# Project-TSC.net
KiCad netlist of a schematic drawn in EAGLE
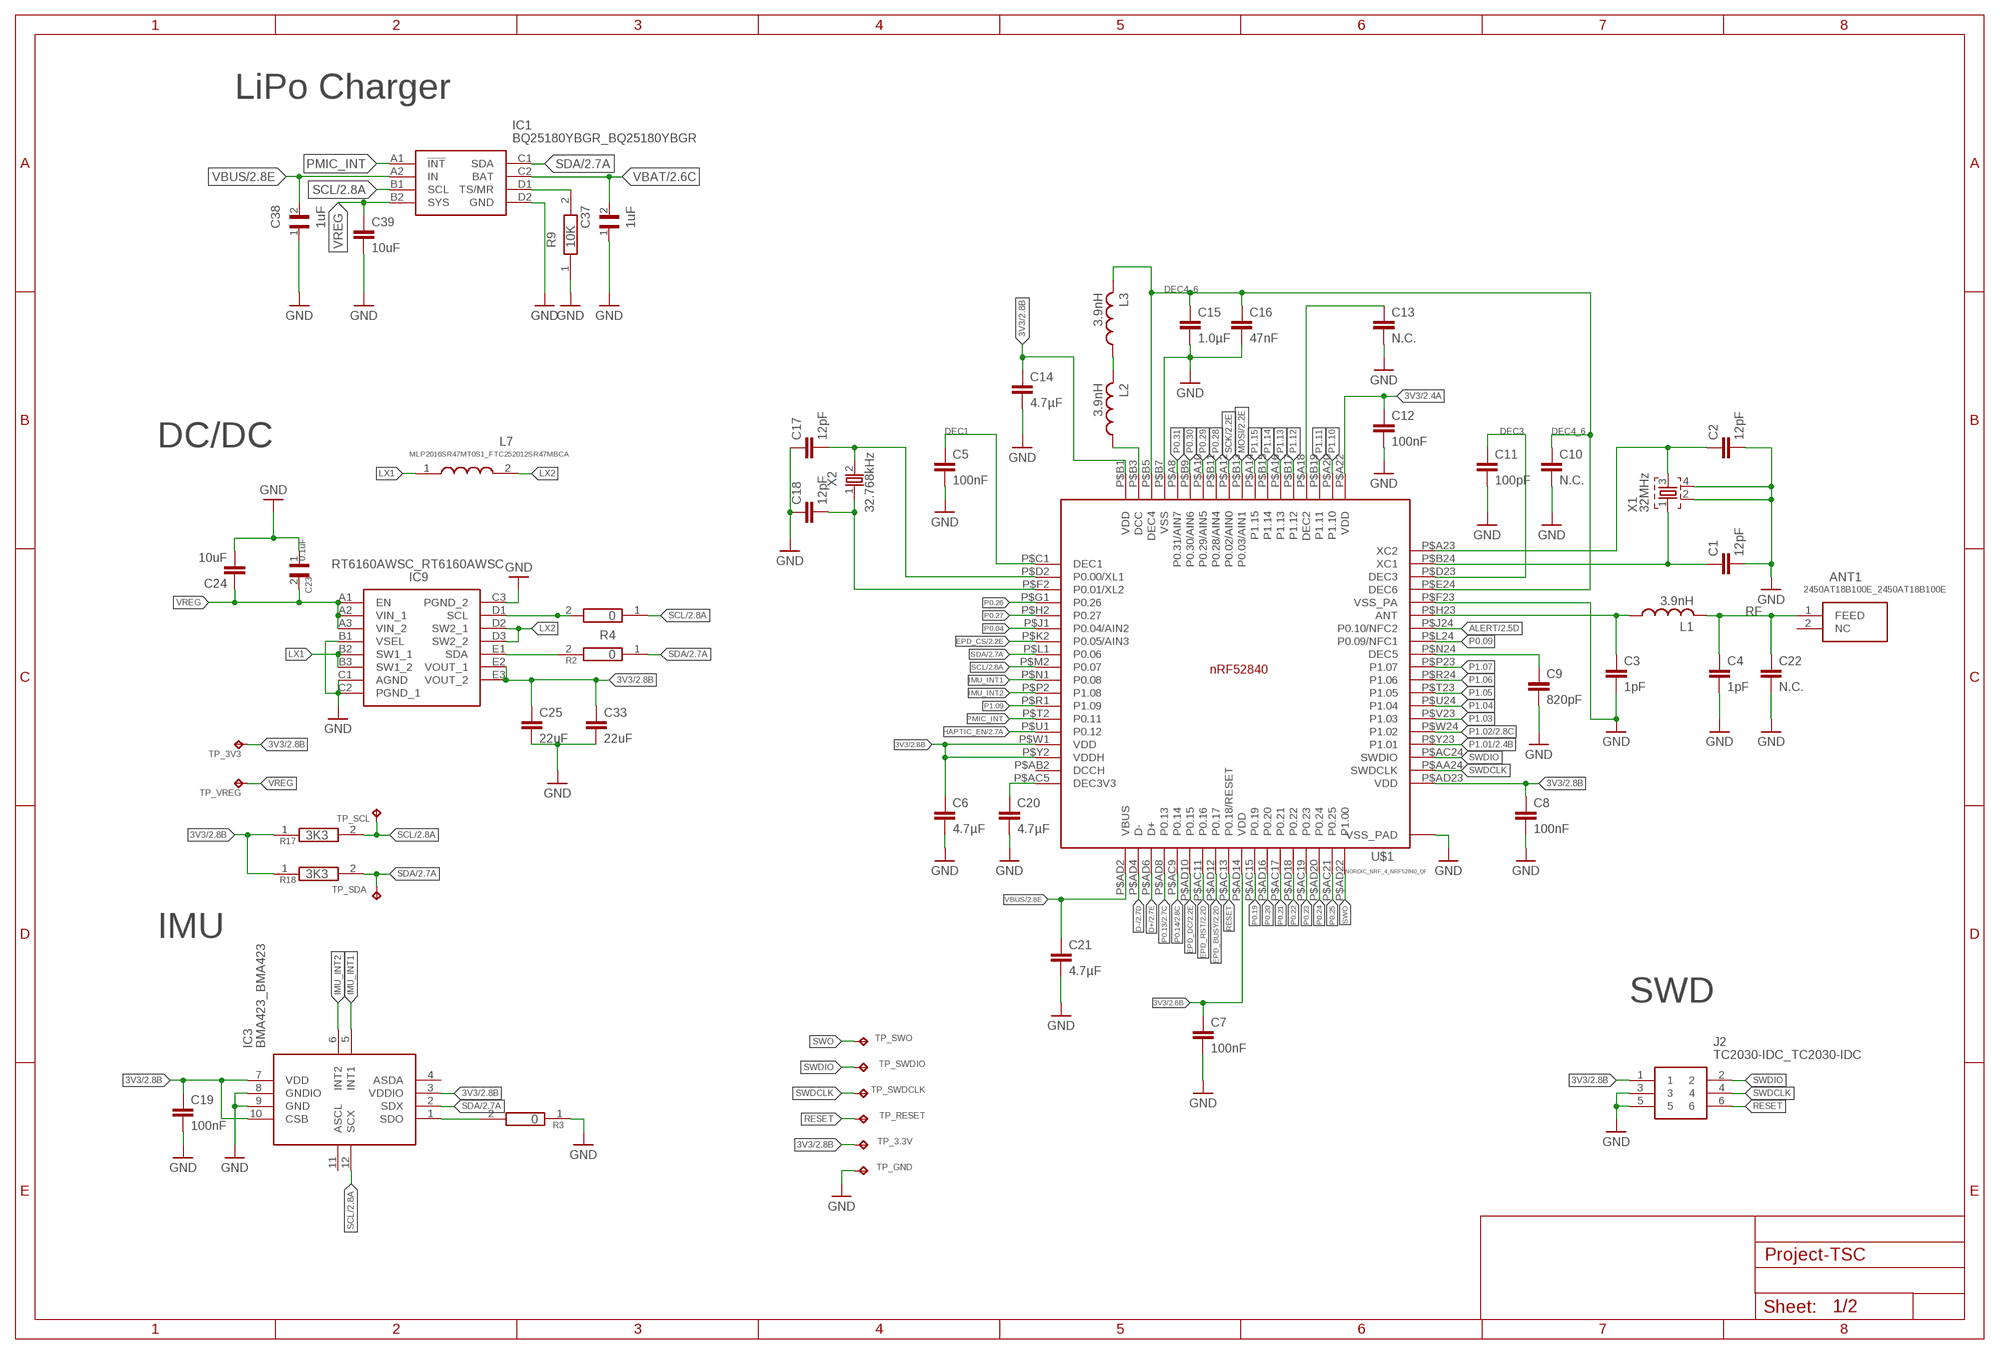
[diagram p0: schematic, sheet 1]
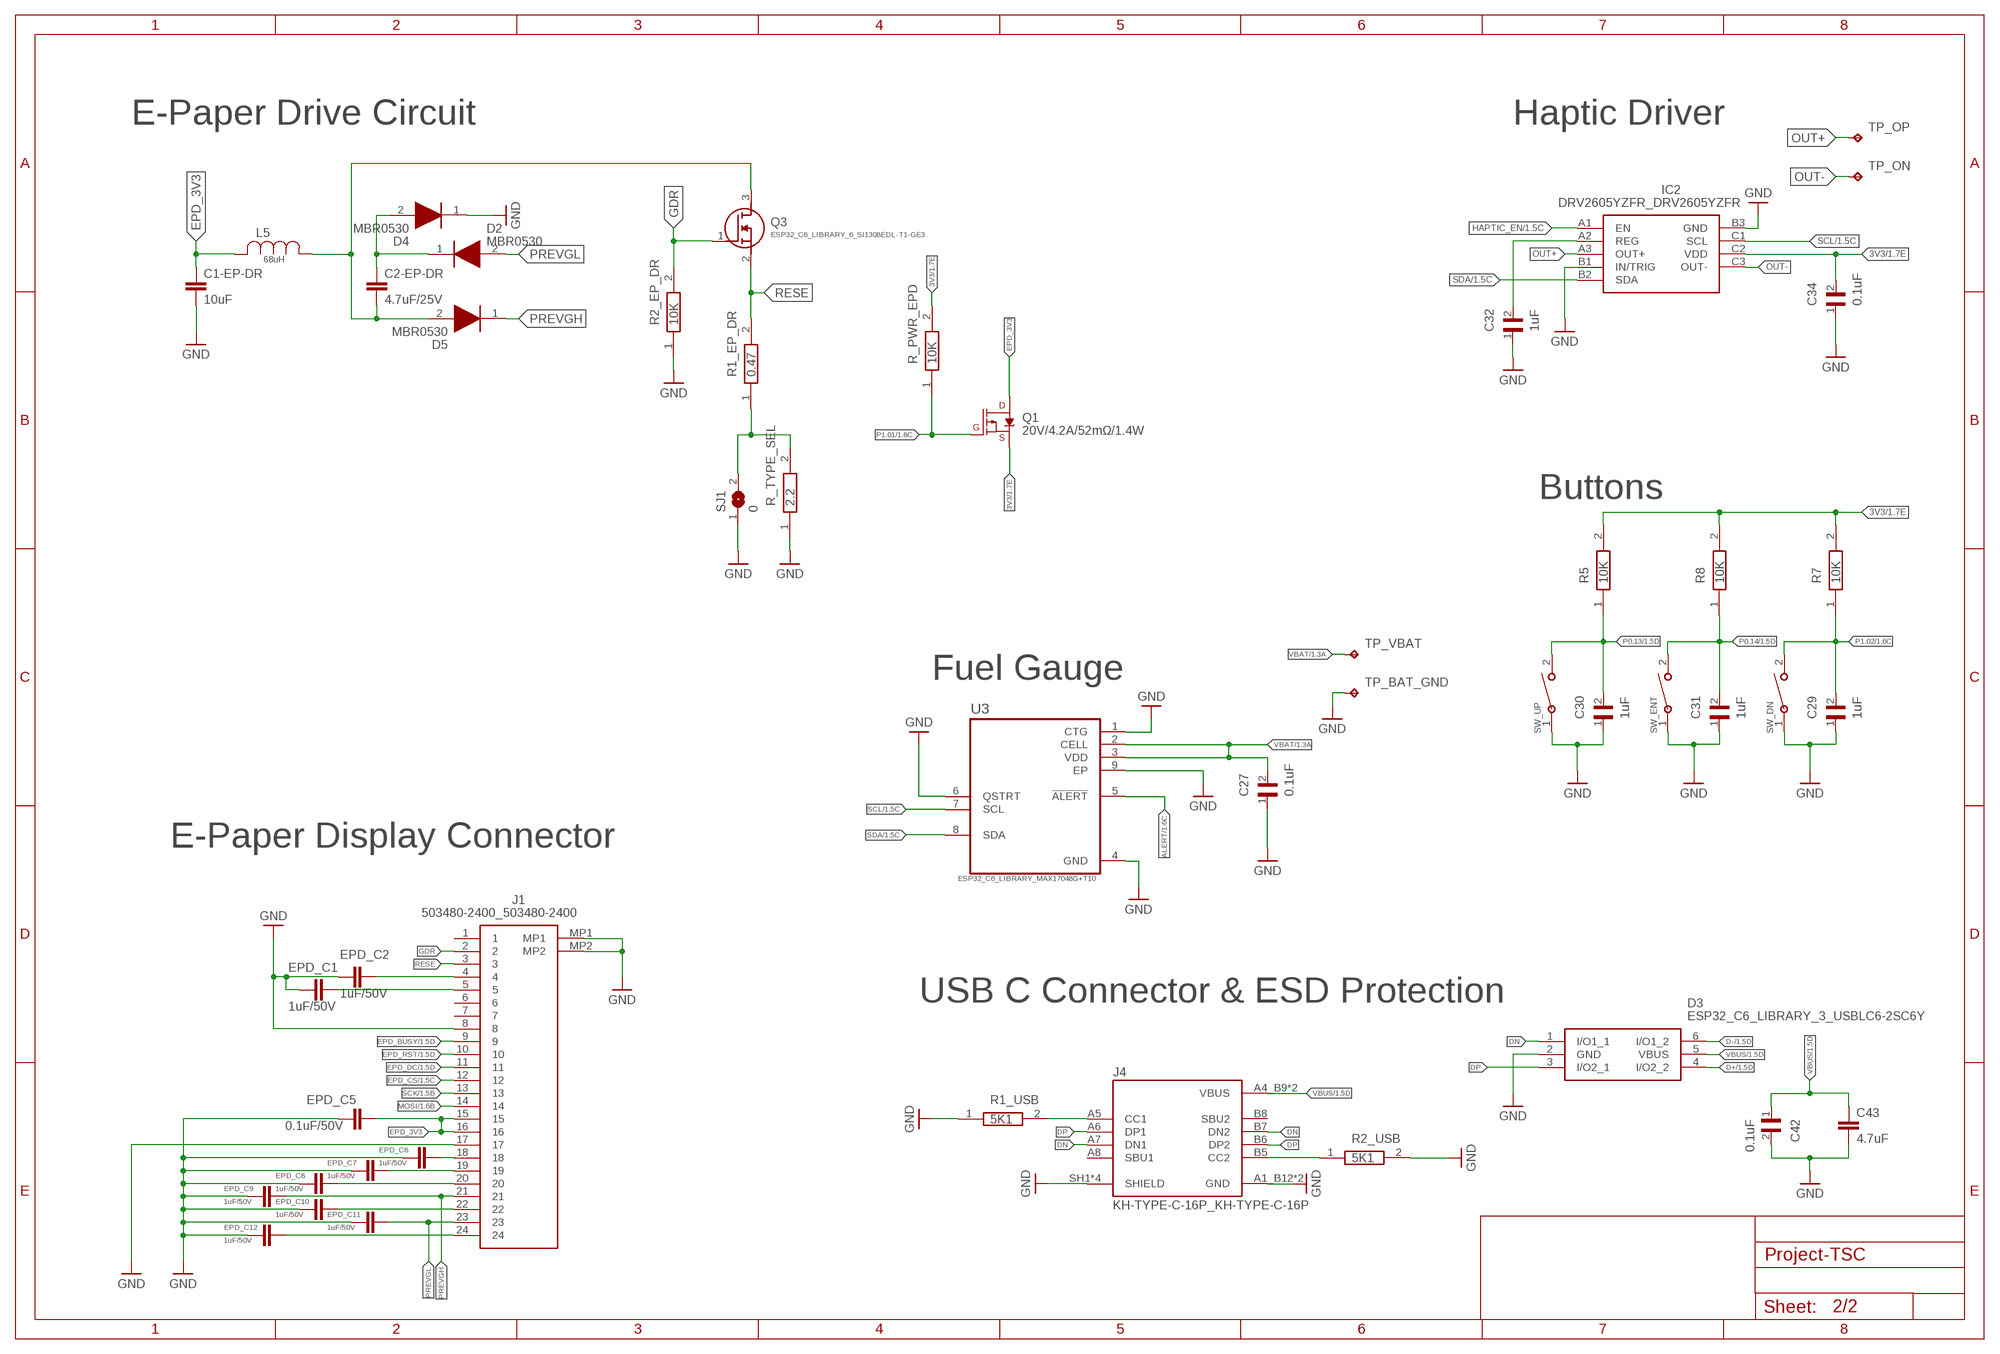
[diagram p1: schematic, sheet 2]

(export (version "E")
  (design (tool "Eeschema 10.0.6"))
  (components
    (comp (ref "ANT1")
      (value "2450AT18B100E_2450AT18B100E")
      (footprint "eagle-import:2450AT18B100E_ANTC3216X140N")
      (fields
        (field (name "ARROW_PART_NUMBER") "2450AT18B100E")
        (field (name "MOUSER_PART_NUMBER") "609-2450AT18B100E")
      )
      (libsource (lib "eagle-import") (part "2450AT18B100E_2450AT18B100E"))
    )
    (comp (ref "C1")
      (value "12pF")
      (footprint "eagle-import:NORDIC_NRF_3_RESC0201_L")
      (libsource (lib "eagle-import") (part "NORDIC_NRF_3_CAPACITOR_0201_L"))
    )
    (comp (ref "C2")
      (value "12pF")
      (footprint "eagle-import:NORDIC_NRF_3_RESC0201_L")
      (libsource (lib "eagle-import") (part "NORDIC_NRF_3_CAPACITOR_0201_L"))
    )
    (comp (ref "C3")
      (value "1pF")
      (footprint "eagle-import:NORDIC_NRF_3_RESC0201_L")
      (libsource (lib "eagle-import") (part "NORDIC_NRF_3_CAPACITOR_0201_L"))
    )
    (comp (ref "C4")
      (value "1pF")
      (footprint "eagle-import:NORDIC_NRF_3_RESC0201_L")
      (libsource (lib "eagle-import") (part "NORDIC_NRF_3_CAPACITOR_0201_L"))
    )
    (comp (ref "C5")
      (value "100nF")
      (footprint "eagle-import:NORDIC_NRF_3_RESC0201_L")
      (libsource (lib "eagle-import") (part "NORDIC_NRF_3_CAPACITOR_0201_L"))
    )
    (comp (ref "C6")
      (value "4.7µF")
      (footprint "eagle-import:PERFECT_0402_0402")
      (libsource (lib "eagle-import") (part "PERFECT_0402_CAP_0402"))
    )
    (comp (ref "C7")
      (value "100nF")
      (footprint "eagle-import:NORDIC_NRF_3_RESC0201_L")
      (libsource (lib "eagle-import") (part "NORDIC_NRF_3_CAPACITOR_0201_L"))
    )
    (comp (ref "C8")
      (value "100nF")
      (footprint "eagle-import:NORDIC_NRF_3_RESC0201_L")
      (libsource (lib "eagle-import") (part "NORDIC_NRF_3_CAPACITOR_0201_L"))
    )
    (comp (ref "C9")
      (value "820pF")
      (footprint "eagle-import:NORDIC_NRF_3_RESC0201_L")
      (libsource (lib "eagle-import") (part "NORDIC_NRF_3_CAPACITOR_0201_L"))
    )
    (comp (ref "C10")
      (value "N.C.")
      (footprint "eagle-import:NORDIC_NRF_3_RESC0201_L")
      (libsource (lib "eagle-import") (part "NORDIC_NRF_3_CAPACITOR_0201_L"))
    )
    (comp (ref "C11")
      (value "100pF")
      (footprint "eagle-import:NORDIC_NRF_3_RESC0201_L")
      (libsource (lib "eagle-import") (part "NORDIC_NRF_3_CAPACITOR_0201_L"))
    )
    (comp (ref "C12")
      (value "100nF")
      (footprint "eagle-import:NORDIC_NRF_3_RESC0201_L")
      (libsource (lib "eagle-import") (part "NORDIC_NRF_3_CAPACITOR_0201_L"))
    )
    (comp (ref "C13")
      (value "N.C.")
      (footprint "eagle-import:NORDIC_NRF_3_RESC0201_L")
      (libsource (lib "eagle-import") (part "NORDIC_NRF_3_CAPACITOR_0201_L"))
    )
    (comp (ref "C14")
      (value "4.7µF")
      (footprint "eagle-import:PERFECT_0402_0402")
      (libsource (lib "eagle-import") (part "PERFECT_0402_CAP_0402"))
    )
    (comp (ref "C15")
      (value "1.0µF")
      (footprint "eagle-import:PERFECT_0402_0402")
      (libsource (lib "eagle-import") (part "PERFECT_0402_CAP_0402"))
    )
    (comp (ref "C16")
      (value "47nF")
      (footprint "eagle-import:NORDIC_NRF_3_RESC0201_L")
      (libsource (lib "eagle-import") (part "NORDIC_NRF_3_CAPACITOR_0201_L"))
    )
    (comp (ref "C17")
      (value "12pF")
      (footprint "eagle-import:NORDIC_NRF_3_RESC0201_L")
      (libsource (lib "eagle-import") (part "NORDIC_NRF_3_CAPACITOR_0201_L"))
    )
    (comp (ref "C18")
      (value "12pF")
      (footprint "eagle-import:NORDIC_NRF_3_RESC0201_L")
      (libsource (lib "eagle-import") (part "NORDIC_NRF_3_CAPACITOR_0201_L"))
    )
    (comp (ref "C19")
      (value "100nF")
      (footprint "eagle-import:PERFECT_0402_0402")
      (libsource (lib "eagle-import") (part "PERFECT_0402_CAP_0402"))
    )
    (comp (ref "C20")
      (value "4.7µF")
      (footprint "eagle-import:PERFECT_0402_0402")
      (libsource (lib "eagle-import") (part "PERFECT_0402_CAP_0402"))
    )
    (comp (ref "C21")
      (value "4.7µF")
      (footprint "eagle-import:PERFECT_0402_0402")
      (libsource (lib "eagle-import") (part "PERFECT_0402_CAP_0402"))
    )
    (comp (ref "C22")
      (value "N.C.")
      (footprint "eagle-import:NORDIC_NRF_3_RESC0201_L")
      (libsource (lib "eagle-import") (part "NORDIC_NRF_3_CAPACITOR_0201_L"))
    )
    (comp (ref "C23")
      (value "0.1uF")
      (footprint "eagle-import:GRM011R60J152KE01L_1_0201")
      (libsource (lib "eagle-import") (part "GRM011R60J152KE01L_1_GRM011R60J152KE01L"))
    )
    (comp (ref "C24")
      (value "10uF")
      (footprint "eagle-import:PERFECT_0402_0402")
      (libsource (lib "eagle-import") (part "PERFECT_0402_CAP_0402"))
    )
    (comp (ref "C25")
      (value "22uF")
      (footprint "eagle-import:PERFECT_0402_0402")
      (libsource (lib "eagle-import") (part "PERFECT_0402_CAP_0402"))
    )
    (comp (ref "C33")
      (value "22uF")
      (footprint "eagle-import:PERFECT_0402_0402")
      (libsource (lib "eagle-import") (part "PERFECT_0402_CAP_0402"))
    )
    (comp (ref "C37")
      (value "1uF")
      (footprint "eagle-import:GRM011R60J152KE01L_1_0201")
      (libsource (lib "eagle-import") (part "GRM011R60J152KE01L_1_GRM011R60J152KE01L"))
    )
    (comp (ref "C38")
      (value "1uF")
      (footprint "eagle-import:GRM011R60J152KE01L_1_0201")
      (libsource (lib "eagle-import") (part "GRM011R60J152KE01L_1_GRM011R60J152KE01L"))
    )
    (comp (ref "C39")
      (value "10uF")
      (footprint "eagle-import:PERFECT_0402_0402")
      (libsource (lib "eagle-import") (part "PERFECT_0402_CAP_0402"))
    )
    (comp (ref "IC1")
      (value "BQ25180YBGR_BQ25180YBGR")
      (footprint "eagle-import:BQ25180YBGR_BGA8C40P2X4_100X155X50")
      (fields
        (field (name "ARROW_PART_NUMBER") "BQ25180YBGR")
        (field (name "MOUSER_PART_NUMBER") "595-BQ25180YBGR")
      )
      (libsource (lib "eagle-import") (part "BQ25180YBGR_BQ25180YBGR"))
    )
    (comp (ref "IC3")
      (value "BMA423_BMA423")
      (footprint "eagle-import:BMA423_BMA423")
      (fields (field (name "ARROW_PART_NUMBER") "BMA423") (field (name "MOUSER_PART_NUMBER") "262-BMA423"))
      (libsource (lib "eagle-import") (part "BMA423_BMA423"))
    )
    (comp (ref "IC9")
      (value "RT6160AWSC_RT6160AWSC")
      (footprint "eagle-import:RT6160AWSC_BGA15C40P3X5_140X230X60")
      (fields
        (field (name "MANUFACTURER_PART_NUMBER") "RT6160AWSC")
        (field (name "MOUSER_PART_NUMBER") "835-RT6160AWSC")
      )
      (libsource (lib "eagle-import") (part "RT6160AWSC_RT6160AWSC"))
    )
    (comp (ref "J2")
      (value "TC2030-IDC_TC2030-IDC")
      (footprint "eagle-import:TC2030-IDC_TC2030IDC")
      (fields (field (name "MANUFACTURER_PART_NUMBER") "TC2030-IDC"))
      (libsource (lib "eagle-import") (part "TC2030-IDC_TC2030-IDC"))
    )
    (comp (ref "L1")
      (value "3.9nH")
      (footprint "eagle-import:NORDIC_NRF_2_RESC0402_L")
      (libsource (lib "eagle-import") (part "NORDIC_NRF_2_INDUCTOR_0402_L"))
    )
    (comp (ref "L2")
      (value "3.9nH")
      (footprint "eagle-import:NORDIC_NRF_2_RESC0402_L")
      (libsource (lib "eagle-import") (part "NORDIC_NRF_2_INDUCTOR_0402_L"))
    )
    (comp (ref "L3")
      (value "3.9nH")
      (footprint "eagle-import:NORDIC_NRF_2_RESC0402_L")
      (libsource (lib "eagle-import") (part "NORDIC_NRF_2_INDUCTOR_0402_L"))
    )
    (comp (ref "L7")
      (value "MLP2016SR47MT0S1_FTC252012SR47MBCA")
      (footprint "eagle-import:MLP2016SR47MT0S1_INDC2016X100N")
      (fields (field (name "MANUFACTURER_PART_NUMBER") "FTC252012SR47MBCA"))
      (libsource (lib "eagle-import") (part "MLP2016SR47MT0S1_FTC252012SR47MBCA"))
    )
    (comp (ref "R2")
      (value "0")
      (footprint "eagle-import:CPF0201D7K68C1_0201")
      (libsource (lib "eagle-import") (part "CPF0201D7K68C1_CPF0201D7K68C1"))
    )
    (comp (ref "R3")
      (value "0")
      (footprint "eagle-import:CPF0201D7K68C1_0201")
      (libsource (lib "eagle-import") (part "CPF0201D7K68C1_CPF0201D7K68C1"))
    )
    (comp (ref "R4")
      (value "0")
      (footprint "eagle-import:CPF0201D7K68C1_0201")
      (libsource (lib "eagle-import") (part "CPF0201D7K68C1_CPF0201D7K68C1"))
    )
    (comp (ref "R9")
      (value "10K")
      (footprint "eagle-import:CPF0201D7K68C1_0201")
      (libsource (lib "eagle-import") (part "CPF0201D7K68C1_CPF0201D7K68C1"))
    )
    (comp (ref "R17")
      (value "3K3")
      (footprint "eagle-import:CPF0201D7K68C1_0201")
      (libsource (lib "eagle-import") (part "CPF0201D7K68C1_CPF0201D7K68C1"))
    )
    (comp (ref "R18")
      (value "3K3")
      (footprint "eagle-import:CPF0201D7K68C1_0201")
      (libsource (lib "eagle-import") (part "CPF0201D7K68C1_CPF0201D7K68C1"))
    )
    (comp (ref "TP_3.3V")
      (value "HECTOR_WATCH_1_TPTP20R")
      (footprint "eagle-import:HECTOR_WATCH_1_TP20R")
      (libsource (lib "eagle-import") (part "HECTOR_WATCH_1_TPTP20R"))
    )
    (comp (ref "TP_3V3")
      (value "HECTOR_WATCH_1_TPTP20R")
      (footprint "eagle-import:HECTOR_WATCH_1_TP20R")
      (libsource (lib "eagle-import") (part "HECTOR_WATCH_1_TPTP20R"))
    )
    (comp (ref "TP_GND")
      (value "HECTOR_WATCH_1_TPTP20R")
      (footprint "eagle-import:HECTOR_WATCH_1_TP20R")
      (libsource (lib "eagle-import") (part "HECTOR_WATCH_1_TPTP20R"))
    )
    (comp (ref "TP_RESET")
      (value "HECTOR_WATCH_1_TPTP20R")
      (footprint "eagle-import:HECTOR_WATCH_1_TP20R")
      (libsource (lib "eagle-import") (part "HECTOR_WATCH_1_TPTP20R"))
    )
    (comp (ref "TP_SCL")
      (value "HECTOR_WATCH_1_TPTP20R")
      (footprint "eagle-import:HECTOR_WATCH_1_TP20R")
      (libsource (lib "eagle-import") (part "HECTOR_WATCH_1_TPTP20R"))
    )
    (comp (ref "TP_SDA")
      (value "HECTOR_WATCH_1_TPTP20R")
      (footprint "eagle-import:HECTOR_WATCH_1_TP20R")
      (libsource (lib "eagle-import") (part "HECTOR_WATCH_1_TPTP20R"))
    )
    (comp (ref "TP_SWDCLK")
      (value "HECTOR_WATCH_1_TPTP20R")
      (footprint "eagle-import:HECTOR_WATCH_1_TP20R")
      (libsource (lib "eagle-import") (part "HECTOR_WATCH_1_TPTP20R"))
    )
    (comp (ref "TP_SWDIO")
      (value "HECTOR_WATCH_1_TPTP20R")
      (footprint "eagle-import:HECTOR_WATCH_1_TP20R")
      (libsource (lib "eagle-import") (part "HECTOR_WATCH_1_TPTP20R"))
    )
    (comp (ref "TP_SWO")
      (value "HECTOR_WATCH_1_TPTP20R")
      (footprint "eagle-import:HECTOR_WATCH_1_TP20R")
      (libsource (lib "eagle-import") (part "HECTOR_WATCH_1_TPTP20R"))
    )
    (comp (ref "TP_VREG")
      (value "HECTOR_WATCH_1_TPTP20R")
      (footprint "eagle-import:HECTOR_WATCH_1_TP20R")
      (libsource (lib "eagle-import") (part "HECTOR_WATCH_1_TPTP20R"))
    )
    (comp (ref "U$1")
      (value "NORDIC_NRF_4_NRF52840_QF")
      (footprint "eagle-import:NORDIC_NRF_4_AQFN50P700X700X85_HS-74N")
      (libsource (lib "eagle-import") (part "NORDIC_NRF_4_NRF52840_QF"))
    )
    (comp (ref "X1")
      (value "32MHz")
      (footprint "eagle-import:NORDIC_NRF_BT-XTAL_2016_N")
      (libsource (lib "eagle-import") (part "NORDIC_NRF_XTAL_32MHZ"))
    )
    (comp (ref "X2")
      (value "32.768kHz")
      (footprint "eagle-import:NORDIC_NRF_1_XTAL_3215_N")
      (libsource (lib "eagle-import") (part "NORDIC_NRF_1_XTAL_32KHZ"))
    )
    (comp (ref "C1-EP-DR")
      (value "10uF")
      (footprint "eagle-import:PERFECT_0402_0402")
      (libsource (lib "eagle-import") (part "PERFECT_0402_CAP_0402"))
    )
    (comp (ref "C2-EP-DR")
      (value "4.7uF/25V")
      (footprint "eagle-import:PERFECT_0402_0402")
      (libsource (lib "eagle-import") (part "PERFECT_0402_CAP_0402"))
    )
    (comp (ref "C27")
      (value "0.1uF")
      (footprint "eagle-import:GRM011R60J152KE01L_2_CAPC0201X13N")
      (fields (field (name "MF") "Murata") (field (name "MP") "GRM011R60J152KE01L"))
      (libsource (lib "eagle-import") (part "GRM011R60J152KE01L_2_GRM011R60J152KE01L"))
    )
    (comp (ref "C29")
      (value "1uF")
      (footprint "eagle-import:GRM011R60J152KE01L_2_CAPC0201X13N")
      (fields (field (name "MF") "Murata") (field (name "MP") "GRM011R60J152KE01L"))
      (libsource (lib "eagle-import") (part "GRM011R60J152KE01L_2_GRM011R60J152KE01L"))
    )
    (comp (ref "C30")
      (value "1uF")
      (footprint "eagle-import:GRM011R60J152KE01L_2_CAPC0201X13N")
      (fields (field (name "MF") "Murata") (field (name "MP") "GRM011R60J152KE01L"))
      (libsource (lib "eagle-import") (part "GRM011R60J152KE01L_2_GRM011R60J152KE01L"))
    )
    (comp (ref "C31")
      (value "1uF")
      (footprint "eagle-import:GRM011R60J152KE01L_2_CAPC0201X13N")
      (fields (field (name "MF") "Murata") (field (name "MP") "GRM011R60J152KE01L"))
      (libsource (lib "eagle-import") (part "GRM011R60J152KE01L_2_GRM011R60J152KE01L"))
    )
    (comp (ref "C32")
      (value "1uF")
      (footprint "eagle-import:GRM011R60J152KE01L_2_CAPC0201X13N")
      (fields (field (name "MF") "Murata") (field (name "MP") "GRM011R60J152KE01L"))
      (libsource (lib "eagle-import") (part "GRM011R60J152KE01L_2_GRM011R60J152KE01L"))
    )
    (comp (ref "C34")
      (value "0.1uF")
      (footprint "eagle-import:GRM011R60J152KE01L_2_CAPC0201X13N")
      (fields (field (name "MF") "Murata") (field (name "MP") "GRM011R60J152KE01L"))
      (libsource (lib "eagle-import") (part "GRM011R60J152KE01L_2_GRM011R60J152KE01L"))
    )
    (comp (ref "C42")
      (value "0.1uF")
      (footprint "eagle-import:GRM011R60J152KE01L_2_CAPC0201X13N")
      (fields (field (name "MF") "Murata") (field (name "MP") "GRM011R60J152KE01L"))
      (libsource (lib "eagle-import") (part "GRM011R60J152KE01L_2_GRM011R60J152KE01L"))
    )
    (comp (ref "C43")
      (value "4.7uF")
      (footprint "eagle-import:PERFECT_0402_0402")
      (libsource (lib "eagle-import") (part "PERFECT_0402_CAP_0402"))
    )
    (comp (ref "D2")
      (value "MBR0530")
      (footprint "eagle-import:ESP32_C6_LIBRARY_5_SOD3716X135N")
      (fields (field (name "MF") "ON Semiconductor"))
      (libsource (lib "eagle-import") (part "ESP32_C6_LIBRARY_5_MBR0530"))
    )
    (comp (ref "D3")
      (value "ESP32_C6_LIBRARY_3_USBLC6-2SC6Y")
      (footprint "eagle-import:ESP32_C6_LIBRARY_3_SOT95P280X145-6N")
      (fields (field (name "MF") "STMicroelectronics") (field (name "MP") "USBLC6-2SC6Y"))
      (libsource (lib "eagle-import") (part "ESP32_C6_LIBRARY_3_USBLC6-2SC6Y"))
    )
    (comp (ref "D4")
      (value "MBR0530")
      (footprint "eagle-import:ESP32_C6_LIBRARY_5_SOD3716X135N")
      (fields (field (name "MF") "ON Semiconductor"))
      (libsource (lib "eagle-import") (part "ESP32_C6_LIBRARY_5_MBR0530"))
    )
    (comp (ref "D5")
      (value "MBR0530")
      (footprint "eagle-import:ESP32_C6_LIBRARY_5_SOD3716X135N")
      (fields (field (name "MF") "ON Semiconductor"))
      (libsource (lib "eagle-import") (part "ESP32_C6_LIBRARY_5_MBR0530"))
    )
    (comp (ref "EPD_C1")
      (value "1uF/50V")
      (footprint "eagle-import:PERFECT_0402_0402")
      (libsource (lib "eagle-import") (part "PERFECT_0402_CAP_0402"))
    )
    (comp (ref "EPD_C2")
      (value "1uF/50V")
      (footprint "eagle-import:PERFECT_0402_0402")
      (libsource (lib "eagle-import") (part "PERFECT_0402_CAP_0402"))
    )
    (comp (ref "EPD_C5")
      (value "0.1uF/50V")
      (footprint "eagle-import:NORDIC_NRF_3_RESC0201_L")
      (libsource (lib "eagle-import") (part "NORDIC_NRF_3_CAPACITOR_0201_L"))
    )
    (comp (ref "EPD_C6")
      (value "1uF/50V")
      (footprint "eagle-import:PERFECT_0402_0402")
      (libsource (lib "eagle-import") (part "PERFECT_0402_CAP_0402"))
    )
    (comp (ref "EPD_C7")
      (value "1uF/50V")
      (footprint "eagle-import:PERFECT_0402_0402")
      (libsource (lib "eagle-import") (part "PERFECT_0402_CAP_0402"))
    )
    (comp (ref "EPD_C8")
      (value "1uF/50V")
      (footprint "eagle-import:PERFECT_0402_0402")
      (libsource (lib "eagle-import") (part "PERFECT_0402_CAP_0402"))
    )
    (comp (ref "EPD_C9")
      (value "1uF/50V")
      (footprint "eagle-import:PERFECT_0402_0402")
      (libsource (lib "eagle-import") (part "PERFECT_0402_CAP_0402"))
    )
    (comp (ref "EPD_C10")
      (value "1uF/50V")
      (footprint "eagle-import:PERFECT_0402_0402")
      (libsource (lib "eagle-import") (part "PERFECT_0402_CAP_0402"))
    )
    (comp (ref "EPD_C11")
      (value "1uF/50V")
      (footprint "eagle-import:PERFECT_0402_0402")
      (libsource (lib "eagle-import") (part "PERFECT_0402_CAP_0402"))
    )
    (comp (ref "EPD_C12")
      (value "1uF/50V")
      (footprint "eagle-import:PERFECT_0402_0402")
      (libsource (lib "eagle-import") (part "PERFECT_0402_CAP_0402"))
    )
    (comp (ref "IC2")
      (value "DRV2605YZFR_DRV2605YZFR")
      (footprint "eagle-import:DRV2605YZFR_BGA9C50P3X3_144X144X62")
      (fields (field (name "ARROW_PART_NUMBER") "DRV2605YZFR"))
      (libsource (lib "eagle-import") (part "DRV2605YZFR_DRV2605YZFR"))
    )
    (comp (ref "J1")
      (value "503480-2400_503480-2400")
      (footprint "eagle-import:503480-2400_5034802400")
      (fields
        (field (name "MANUFACTURER_PART_NUMBER") "503480-2400")
        (field (name "MOUSER_PART_NUMBER") "538-503480-2400")
      )
      (libsource (lib "eagle-import") (part "503480-2400_503480-2400"))
    )
    (comp (ref "J4")
      (value "KH-TYPE-C-16P_KH-TYPE-C-16P")
      (footprint "eagle-import:KH-TYPE-C-16P_KINGHELM_KH-TYPE-C-16P")
      (fields (field (name "MF") "kinghelm") (field (name "MP") "KH-TYPE-C-16P"))
      (libsource (lib "eagle-import") (part "KH-TYPE-C-16P_KH-TYPE-C-16P"))
    )
    (comp (ref "L5")
      (value "68uH")
      (footprint "eagle-import:ESP32_C6_LIBRARY_2_IND_4828-WE-TPC_WRE")
      (fields
        (field (name "MANUFACTURER_PART_NUMBER") "744043680")
        (field (name "COPYRIGHT") "Copyright (C) 2024 Ultra Librarian. All rights reserved.")
      )
      (libsource (lib "eagle-import") (part "ESP32_C6_LIBRARY_2_744043680IND_4828-WE-TPC_WRE"))
    )
    (comp (ref "Q1")
      (value "20V/4.2A/52mΩ/1.4W")
      (footprint "eagle-import:ESP32_C6_LIBRARY_4_ESP32_C6_LIBRARY_4_ESP32_C6_LIBRARY_4_ESP32_C6_LIBRARY_4_ESP32_WROVER_SPARKFUN-DISCRETESEMI_SOT23-3")
      (libsource (lib "eagle-import") (part "ESP32_C6_LIBRARY_4_ESP32_WROVER_SPARKFUN-DISCRETESEMI_MOSFET_PCH-DMG2305UX-7"))
    )
    (comp (ref "Q3")
      (value "ESP32_C6_LIBRARY_6_SI1308EDL-T1-GE3")
      (footprint "eagle-import:ESP32_C6_LIBRARY_6_SOT65P210X110-3N")
      (fields (field (name "MF") "Vishay Siliconix") (field (name "MP") "SI1308EDL-T1-GE3"))
      (libsource (lib "eagle-import") (part "ESP32_C6_LIBRARY_6_SI1308EDL-T1-GE3"))
    )
    (comp (ref "R1_EP_DR")
      (value "0.47")
      (footprint "eagle-import:CPF0201D7K68C1_0201")
      (libsource (lib "eagle-import") (part "CPF0201D7K68C1_CPF0201D7K68C1"))
    )
    (comp (ref "R1_USB")
      (value "5K1")
      (footprint "eagle-import:CPF0201D7K68C1_0201")
      (libsource (lib "eagle-import") (part "CPF0201D7K68C1_CPF0201D7K68C1"))
    )
    (comp (ref "R2_EP_DR")
      (value "10K")
      (footprint "eagle-import:CPF0201D7K68C1_0201")
      (libsource (lib "eagle-import") (part "CPF0201D7K68C1_CPF0201D7K68C1"))
    )
    (comp (ref "R2_USB")
      (value "5K1")
      (footprint "eagle-import:CPF0201D7K68C1_0201")
      (libsource (lib "eagle-import") (part "CPF0201D7K68C1_CPF0201D7K68C1"))
    )
    (comp (ref "R5")
      (value "10K")
      (footprint "eagle-import:CPF0201D7K68C1_0201")
      (libsource (lib "eagle-import") (part "CPF0201D7K68C1_CPF0201D7K68C1"))
    )
    (comp (ref "R7")
      (value "10K")
      (footprint "eagle-import:CPF0201D7K68C1_0201")
      (libsource (lib "eagle-import") (part "CPF0201D7K68C1_CPF0201D7K68C1"))
    )
    (comp (ref "R8")
      (value "10K")
      (footprint "eagle-import:CPF0201D7K68C1_0201")
      (libsource (lib "eagle-import") (part "CPF0201D7K68C1_CPF0201D7K68C1"))
    )
    (comp (ref "R_PWR_EPD")
      (value "10K")
      (footprint "eagle-import:CPF0201D7K68C1_0201")
      (libsource (lib "eagle-import") (part "CPF0201D7K68C1_CPF0201D7K68C1"))
    )
    (comp (ref "R_TYPE_SEL")
      (value "2.2")
      (footprint "eagle-import:CPF0201D7K68C1_0201")
      (libsource (lib "eagle-import") (part "CPF0201D7K68C1_CPF0201D7K68C1"))
    )
    (comp (ref "SJ1")
      (value "0")
      (footprint "eagle-import:ESP32_C6_LIBRARY_7_JUMPER_SJ")
      (libsource (lib "eagle-import") (part "ESP32_C6_LIBRARY_7_JUMPER_SJ"))
    )
    (comp (ref "SW_DN")
      (value "2025-10-22_07-23-44_LIBRARY_EVP-AKE31ASW_EVP-AKE31A_PAN")
      (footprint "eagle-import:2025-10-22_07-23-44_LIBRARY_SW_EVP-AKE31A_PAN")
      (fields
        (field (name "MANUFACTURER_PART_NUMBER") "EVP-AKE31A")
        (field (name "COPYRIGHT") "Copyright (C) 2025 Ultra Librarian. All rights reserved.")
      )
      (libsource (lib "eagle-import") (part "2025-10-22_07-23-44_LIBRARY_EVP-AKE31ASW_EVP-AKE31A_PAN"))
    )
    (comp (ref "SW_ENT")
      (value "2025-10-22_07-23-44_LIBRARY_EVP-AKE31ASW_EVP-AKE31A_PAN")
      (footprint "eagle-import:2025-10-22_07-23-44_LIBRARY_SW_EVP-AKE31A_PAN")
      (fields
        (field (name "MANUFACTURER_PART_NUMBER") "EVP-AKE31A")
        (field (name "COPYRIGHT") "Copyright (C) 2025 Ultra Librarian. All rights reserved.")
      )
      (libsource (lib "eagle-import") (part "2025-10-22_07-23-44_LIBRARY_EVP-AKE31ASW_EVP-AKE31A_PAN"))
    )
    (comp (ref "SW_UP")
      (value "2025-10-22_07-23-44_LIBRARY_EVP-AKE31ASW_EVP-AKE31A_PAN")
      (footprint "eagle-import:2025-10-22_07-23-44_LIBRARY_SW_EVP-AKE31A_PAN")
      (fields
        (field (name "MANUFACTURER_PART_NUMBER") "EVP-AKE31A")
        (field (name "COPYRIGHT") "Copyright (C) 2025 Ultra Librarian. All rights reserved.")
      )
      (libsource (lib "eagle-import") (part "2025-10-22_07-23-44_LIBRARY_EVP-AKE31ASW_EVP-AKE31A_PAN"))
    )
    (comp (ref "TP_BAT_GND")
      (value "HECTOR_WATCH_1_TPTP20R")
      (footprint "eagle-import:HECTOR_WATCH_1_TP20R")
      (libsource (lib "eagle-import") (part "HECTOR_WATCH_1_TPTP20R"))
    )
    (comp (ref "TP_ON")
      (value "HECTOR_WATCH_1_TPTP20R")
      (footprint "eagle-import:HECTOR_WATCH_1_TP20R")
      (libsource (lib "eagle-import") (part "HECTOR_WATCH_1_TPTP20R"))
    )
    (comp (ref "TP_OP")
      (value "HECTOR_WATCH_1_TPTP20R")
      (footprint "eagle-import:HECTOR_WATCH_1_TP20R")
      (libsource (lib "eagle-import") (part "HECTOR_WATCH_1_TPTP20R"))
    )
    (comp (ref "TP_VBAT")
      (value "HECTOR_WATCH_1_TPTP20R")
      (footprint "eagle-import:HECTOR_WATCH_1_TP20R")
      (libsource (lib "eagle-import") (part "HECTOR_WATCH_1_TPTP20R"))
    )
    (comp (ref "U3")
      (value "ESP32_C6_LIBRARY_MAX17048G+T10")
      (footprint "eagle-import:ESP32_C6_LIBRARY_SON50P200X200X80-9N")
      (fields (field (name "MF") "Analog Devices") (field (name "MP") "MAX17048G+T10"))
      (libsource (lib "eagle-import") (part "ESP32_C6_LIBRARY_MAX17048G+T10"))
    )
  )
  (nets
    (net (code "1") (name "3V3") (class "Default")
      (node (ref "C14") (pin "1") (pinfunction "1_1") (pintype "passive"))
      (node (ref "C19") (pin "1") (pinfunction "1_1") (pintype "passive"))
      (node (ref "C25") (pin "1") (pinfunction "1_1") (pintype "passive"))
      (node (ref "C33") (pin "1") (pinfunction "1_1") (pintype "passive"))
      (node (ref "C34") (pin "2") (pinfunction "2_2") (pintype "passive"))
      (node (ref "C6") (pin "1") (pinfunction "1_1") (pintype "passive"))
      (node (ref "C7") (pin "1") (pinfunction "1_1") (pintype "passive"))
      (node (ref "C8") (pin "1") (pinfunction "1_1") (pintype "passive"))
      (node (ref "IC2") (pin "C2") (pinfunction "VDD_C2") (pintype "bidirectional"))
      (node (ref "IC3") (pin "10") (pinfunction "CSB_10") (pintype "bidirectional"))
      (node (ref "IC3") (pin "3") (pinfunction "VDDIO_3") (pintype "bidirectional"))
      (node (ref "IC3") (pin "7") (pinfunction "VDD_7") (pintype "bidirectional"))
      (node (ref "IC9") (pin "E2") (pinfunction "VOUT_1_E2") (pintype "bidirectional"))
      (node (ref "IC9") (pin "E3") (pinfunction "VOUT_2_E3") (pintype "bidirectional"))
      (node (ref "J2") (pin "1") (pinfunction "1_1") (pintype "bidirectional"))
      (node (ref "Q1") (pin "2") (pinfunction "S_2") (pintype "bidirectional"))
      (node (ref "R17") (pin "1") (pinfunction "1_1") (pintype "bidirectional"))
      (node (ref "R18") (pin "1") (pinfunction "1_1") (pintype "bidirectional"))
      (node (ref "R5") (pin "2") (pinfunction "2_2") (pintype "bidirectional"))
      (node (ref "R7") (pin "2") (pinfunction "2_2") (pintype "bidirectional"))
      (node (ref "R8") (pin "2") (pinfunction "2_2") (pintype "bidirectional"))
      (node (ref "R_PWR_EPD") (pin "2") (pinfunction "2_2") (pintype "bidirectional"))
      (node (ref "TP_3.3V") (pin "TP") (pinfunction "TP_TP") (pintype "input"))
      (node (ref "TP_3V3") (pin "TP") (pinfunction "TP_TP") (pintype "input"))
      (node (ref "U$1") (pin "P$AD14") (pinfunction "VDD_P$AD14") (pintype "power_in"))
      (node (ref "U$1") (pin "P$AD23") (pinfunction "VDD_P$AD23") (pintype "power_in"))
      (node (ref "U$1") (pin "P$B1") (pinfunction "VDD_P$B1") (pintype "power_in"))
      (node (ref "U$1") (pin "P$W1") (pinfunction "VDD_P$W1") (pintype "power_in"))
      (node (ref "U$1") (pin "P$Y2") (pinfunction "VDDH_P$Y2") (pintype "power_in"))
    )
    (net (code "2") (name "3V3{slash}2.4A") (class "Default")
      (node (ref "C12") (pin "1") (pinfunction "1_1") (pintype "passive"))
      (node (ref "U$1") (pin "P$A22") (pinfunction "VDD_P$A22") (pintype "power_in"))
    )
    (net (code "3") (name "ALERT") (class "Default")
      (node (ref "U$1") (pin "P$J24") (pinfunction "P0.10/NFC2_P$J24") (pintype "bidirectional"))
      (node (ref "U3") (pin "5") (pinfunction "~{ALERT}_5") (pintype "output"))
    )
    (net (code "4") (name "D+") (class "Default")
      (node (ref "D3") (pin "4") (pinfunction "I/O2_2_4") (pintype "bidirectional"))
      (node (ref "U$1") (pin "P$AD6") (pinfunction "D+_P$AD6") (pintype "bidirectional"))
    )
    (net (code "5") (name "D-") (class "Default")
      (node (ref "D3") (pin "6") (pinfunction "I/O1_2_6") (pintype "bidirectional"))
      (node (ref "U$1") (pin "P$AD4") (pinfunction "D-_P$AD4") (pintype "bidirectional"))
    )
    (net (code "6") (name "DEC1") (class "Default")
      (node (ref "C5") (pin "1") (pinfunction "1_1") (pintype "passive"))
      (node (ref "U$1") (pin "P$C1") (pinfunction "DEC1_P$C1") (pintype "power_in"))
    )
    (net (code "7") (name "DEC3") (class "Default")
      (node (ref "C11") (pin "1") (pinfunction "1_1") (pintype "passive"))
      (node (ref "U$1") (pin "P$D23") (pinfunction "DEC3_P$D23") (pintype "bidirectional"))
    )
    (net (code "8") (name "DEC4_6") (class "Default")
      (node (ref "C10") (pin "1") (pinfunction "1_1") (pintype "passive"))
      (node (ref "C15") (pin "1") (pinfunction "1_1") (pintype "passive"))
      (node (ref "C16") (pin "1") (pinfunction "1_1") (pintype "passive"))
      (node (ref "L3") (pin "2") (pinfunction "2_2") (pintype "passive"))
      (node (ref "U$1") (pin "P$B5") (pinfunction "DEC4_P$B5") (pintype "power_in"))
      (node (ref "U$1") (pin "P$E24") (pinfunction "DEC6_P$E24") (pintype "bidirectional"))
    )
    (net (code "9") (name "DN") (class "Default")
      (node (ref "D3") (pin "1") (pinfunction "I/O1_1_1") (pintype "bidirectional"))
      (node (ref "J4") (pin "A7") (pinfunction "DN1_A7") (pintype "bidirectional"))
      (node (ref "J4") (pin "B7") (pinfunction "DN2_B7") (pintype "bidirectional"))
    )
    (net (code "10") (name "DP") (class "Default")
      (node (ref "D3") (pin "3") (pinfunction "I/O2_1_3") (pintype "bidirectional"))
      (node (ref "J4") (pin "A6") (pinfunction "DP1_A6") (pintype "bidirectional"))
      (node (ref "J4") (pin "B6") (pinfunction "DP2_B6") (pintype "bidirectional"))
    )
    (net (code "11") (name "EPD_3V3") (class "Default")
      (node (ref "C1-EP-DR") (pin "1") (pinfunction "1_1") (pintype "passive"))
      (node (ref "EPD_C5") (pin "2") (pinfunction "2_2") (pintype "passive"))
      (node (ref "J1") (pin "15") (pinfunction "15_15") (pintype "bidirectional"))
      (node (ref "J1") (pin "16") (pinfunction "16_16") (pintype "bidirectional"))
      (node (ref "L5") (pin "2") (pinfunction "2_2") (pintype "passive"))
      (node (ref "Q1") (pin "3") (pinfunction "D_3") (pintype "bidirectional"))
    )
    (net (code "12") (name "EPD_BUSY") (class "Default")
      (node (ref "J1") (pin "9") (pinfunction "9_9") (pintype "bidirectional"))
      (node (ref "U$1") (pin "P$AD12") (pinfunction "P0.17_P$AD12") (pintype "bidirectional"))
    )
    (net (code "13") (name "EPD_CS") (class "Default")
      (node (ref "J1") (pin "12") (pinfunction "12_12") (pintype "bidirectional"))
      (node (ref "U$1") (pin "P$K2") (pinfunction "P0.05/AIN3_P$K2") (pintype "bidirectional"))
    )
    (net (code "14") (name "EPD_DC") (class "Default")
      (node (ref "J1") (pin "11") (pinfunction "11_11") (pintype "bidirectional"))
      (node (ref "U$1") (pin "P$AD10") (pinfunction "P0.15_P$AD10") (pintype "bidirectional"))
    )
    (net (code "15") (name "EPD_RST") (class "Default")
      (node (ref "J1") (pin "10") (pinfunction "10_10") (pintype "bidirectional"))
      (node (ref "U$1") (pin "P$AC11") (pinfunction "P0.16_P$AC11") (pintype "bidirectional"))
    )
    (net (code "16") (name "GDR") (class "Default")
      (node (ref "J1") (pin "2") (pinfunction "2_2") (pintype "bidirectional"))
      (node (ref "Q3") (pin "1") (pinfunction "G_1") (pintype "bidirectional"))
      (node (ref "R2_EP_DR") (pin "2") (pinfunction "2_2") (pintype "bidirectional"))
    )
    (net (code "17") (name "GND") (class "Default")
      (node (ref "C1") (pin "2") (pinfunction "2_2") (pintype "passive"))
      (node (ref "C1-EP-DR") (pin "2") (pinfunction "2_2") (pintype "passive"))
      (node (ref "C10") (pin "2") (pinfunction "2_2") (pintype "passive"))
      (node (ref "C11") (pin "2") (pinfunction "2_2") (pintype "passive"))
      (node (ref "C12") (pin "2") (pinfunction "2_2") (pintype "passive"))
      (node (ref "C13") (pin "2") (pinfunction "2_2") (pintype "passive"))
      (node (ref "C14") (pin "2") (pinfunction "2_2") (pintype "passive"))
      (node (ref "C15") (pin "2") (pinfunction "2_2") (pintype "passive"))
      (node (ref "C16") (pin "2") (pinfunction "2_2") (pintype "passive"))
      (node (ref "C17") (pin "1") (pinfunction "1_1") (pintype "passive"))
      (node (ref "C18") (pin "1") (pinfunction "1_1") (pintype "passive"))
      (node (ref "C19") (pin "2") (pinfunction "2_2") (pintype "passive"))
      (node (ref "C2") (pin "2") (pinfunction "2_2") (pintype "passive"))
      (node (ref "C20") (pin "2") (pinfunction "2_2") (pintype "passive"))
      (node (ref "C21") (pin "2") (pinfunction "2_2") (pintype "passive"))
      (node (ref "C22") (pin "2") (pinfunction "2_2") (pintype "passive"))
      (node (ref "C23") (pin "1") (pinfunction "1_1") (pintype "passive"))
      (node (ref "C24") (pin "2") (pinfunction "2_2") (pintype "passive"))
      (node (ref "C25") (pin "2") (pinfunction "2_2") (pintype "passive"))
      (node (ref "C27") (pin "1") (pinfunction "1_1") (pintype "passive"))
      (node (ref "C29") (pin "1") (pinfunction "1_1") (pintype "passive"))
      (node (ref "C3") (pin "2") (pinfunction "2_2") (pintype "passive"))
      (node (ref "C30") (pin "1") (pinfunction "1_1") (pintype "passive"))
      (node (ref "C31") (pin "1") (pinfunction "1_1") (pintype "passive"))
      (node (ref "C32") (pin "1") (pinfunction "1_1") (pintype "passive"))
      (node (ref "C33") (pin "2") (pinfunction "2_2") (pintype "passive"))
      (node (ref "C34") (pin "1") (pinfunction "1_1") (pintype "passive"))
      (node (ref "C37") (pin "1") (pinfunction "1_1") (pintype "passive"))
      (node (ref "C38") (pin "1") (pinfunction "1_1") (pintype "passive"))
      (node (ref "C39") (pin "2") (pinfunction "2_2") (pintype "passive"))
      (node (ref "C4") (pin "2") (pinfunction "2_2") (pintype "passive"))
      (node (ref "C42") (pin "2") (pinfunction "2_2") (pintype "passive"))
      (node (ref "C43") (pin "2") (pinfunction "2_2") (pintype "passive"))
      (node (ref "C5") (pin "2") (pinfunction "2_2") (pintype "passive"))
      (node (ref "C6") (pin "2") (pinfunction "2_2") (pintype "passive"))
      (node (ref "C7") (pin "2") (pinfunction "2_2") (pintype "passive"))
      (node (ref "C8") (pin "2") (pinfunction "2_2") (pintype "passive"))
      (node (ref "C9") (pin "2") (pinfunction "2_2") (pintype "passive"))
      (node (ref "D3") (pin "2") (pinfunction "GND_2") (pintype "bidirectional"))
      (node (ref "D4") (pin "1") (pinfunction "K_1") (pintype "bidirectional"))
      (node (ref "EPD_C1") (pin "2") (pinfunction "2_2") (pintype "passive"))
      (node (ref "EPD_C10") (pin "2") (pinfunction "2_2") (pintype "passive"))
      (node (ref "EPD_C11") (pin "2") (pinfunction "2_2") (pintype "passive"))
      (node (ref "EPD_C12") (pin "2") (pinfunction "2_2") (pintype "passive"))
      (node (ref "EPD_C2") (pin "2") (pinfunction "2_2") (pintype "passive"))
      (node (ref "EPD_C5") (pin "1") (pinfunction "1_1") (pintype "passive"))
      (node (ref "EPD_C6") (pin "2") (pinfunction "2_2") (pintype "passive"))
      (node (ref "EPD_C7") (pin "2") (pinfunction "2_2") (pintype "passive"))
      (node (ref "EPD_C8") (pin "2") (pinfunction "2_2") (pintype "passive"))
      (node (ref "EPD_C9") (pin "2") (pinfunction "2_2") (pintype "passive"))
      (node (ref "IC1") (pin "D2") (pinfunction "GND_D2") (pintype "bidirectional"))
      (node (ref "IC2") (pin "B1") (pinfunction "IN/TRIG_B1") (pintype "bidirectional"))
      (node (ref "IC2") (pin "B3") (pinfunction "GND_B3") (pintype "bidirectional"))
      (node (ref "IC3") (pin "8") (pinfunction "GNDIO_8") (pintype "bidirectional"))
      (node (ref "IC3") (pin "9") (pinfunction "GND_9") (pintype "bidirectional"))
      (node (ref "IC9") (pin "B1") (pinfunction "VSEL_B1") (pintype "bidirectional"))
      (node (ref "IC9") (pin "C1") (pinfunction "AGND_C1") (pintype "bidirectional"))
      (node (ref "IC9") (pin "C2") (pinfunction "PGND_1_C2") (pintype "bidirectional"))
      (node (ref "IC9") (pin "C3") (pinfunction "PGND_2_C3") (pintype "bidirectional"))
      (node (ref "J1") (pin "17") (pinfunction "17_17") (pintype "bidirectional"))
      (node (ref "J1") (pin "8") (pinfunction "8_8") (pintype "bidirectional"))
      (node (ref "J1") (pin "MP1") (pinfunction "MP1_MP1") (pintype "bidirectional"))
      (node (ref "J1") (pin "MP2") (pinfunction "MP2_MP2") (pintype "bidirectional"))
      (node (ref "J2") (pin "3") (pinfunction "3_3") (pintype "bidirectional"))
      (node (ref "J2") (pin "5") (pinfunction "5_5") (pintype "bidirectional"))
      (node (ref "J4") (pin "A12_B1") (pinfunction "GND_A12_B1") (pintype "power_in"))
      (node (ref "J4") (pin "A1_B12") (pinfunction "GND_A1_B12") (pintype "power_in"))
      (node (ref "J4") (pin "SH1") (pinfunction "SHIELD_SH1") (pintype "passive"))
      (node (ref "J4") (pin "SH2") (pinfunction "SHIELD_SH2") (pintype "passive"))
      (node (ref "J4") (pin "SH3") (pinfunction "SHIELD_SH3") (pintype "passive"))
      (node (ref "J4") (pin "SH4") (pinfunction "SHIELD_SH4") (pintype "passive"))
      (node (ref "R1_USB") (pin "1") (pinfunction "1_1") (pintype "bidirectional"))
      (node (ref "R2_EP_DR") (pin "1") (pinfunction "1_1") (pintype "bidirectional"))
      (node (ref "R2_USB") (pin "2") (pinfunction "2_2") (pintype "bidirectional"))
      (node (ref "R3") (pin "1") (pinfunction "1_1") (pintype "bidirectional"))
      (node (ref "R9") (pin "1") (pinfunction "1_1") (pintype "bidirectional"))
      (node (ref "R_TYPE_SEL") (pin "1") (pinfunction "1_1") (pintype "bidirectional"))
      (node (ref "SJ1") (pin "1") (pinfunction "1_1") (pintype "passive"))
      (node (ref "SW_DN") (pin "1") (pinfunction "1_1") (pintype "passive"))
      (node (ref "SW_ENT") (pin "1") (pinfunction "1_1") (pintype "passive"))
      (node (ref "SW_UP") (pin "1") (pinfunction "1_1") (pintype "passive"))
      (node (ref "TP_BAT_GND") (pin "TP") (pinfunction "TP_TP") (pintype "input"))
      (node (ref "TP_GND") (pin "TP") (pinfunction "TP_TP") (pintype "input"))
      (node (ref "U$1") (pin "P$74") (pinfunction "VSS_PAD_P$74") (pintype "bidirectional"))
      (node (ref "U$1") (pin "P$75") (pinfunction "VSS_PAD_P$75") (pintype "bidirectional"))
      (node (ref "U$1") (pin "P$76") (pinfunction "VSS_PAD_P$76") (pintype "bidirectional"))
      (node (ref "U$1") (pin "P$77") (pinfunction "VSS_PAD_P$77") (pintype "bidirectional"))
      (node (ref "U$1") (pin "P$78") (pinfunction "VSS_PAD_P$78") (pintype "bidirectional"))
      (node (ref "U$1") (pin "P$79") (pinfunction "VSS_PAD_P$79") (pintype "bidirectional"))
      (node (ref "U$1") (pin "P$80") (pinfunction "VSS_PAD_P$80") (pintype "bidirectional"))
      (node (ref "U$1") (pin "P$81") (pinfunction "VSS_PAD_P$81") (pintype "bidirectional"))
      (node (ref "U$1") (pin "P$82") (pinfunction "VSS_PAD_P$82") (pintype "bidirectional"))
      (node (ref "U$1") (pin "P$83") (pinfunction "VSS_PAD_P$83") (pintype "bidirectional"))
      (node (ref "U$1") (pin "P$84") (pinfunction "VSS_PAD_P$84") (pintype "bidirectional"))
      (node (ref "U$1") (pin "P$85") (pinfunction "VSS_PAD_P$85") (pintype "bidirectional"))
      (node (ref "U$1") (pin "P$86") (pinfunction "VSS_PAD_P$86") (pintype "bidirectional"))
      (node (ref "U$1") (pin "P$87") (pinfunction "VSS_PAD_P$87") (pintype "bidirectional"))
      (node (ref "U$1") (pin "P$88") (pinfunction "VSS_PAD_P$88") (pintype "bidirectional"))
      (node (ref "U$1") (pin "P$89") (pinfunction "VSS_PAD_P$89") (pintype "bidirectional"))
      (node (ref "U$1") (pin "P$90") (pinfunction "VSS_PAD_P$90") (pintype "bidirectional"))
      (node (ref "U$1") (pin "P$B7") (pinfunction "VSS_P$B7") (pintype "power_in"))
      (node (ref "U$1") (pin "P$F23") (pinfunction "VSS_PA_P$F23") (pintype "bidirectional"))
      (node (ref "U3") (pin "1") (pinfunction "CTG_1") (pintype "power_in"))
      (node (ref "U3") (pin "4") (pinfunction "GND_4") (pintype "power_in"))
      (node (ref "U3") (pin "6") (pinfunction "QSTRT_6") (pintype "input"))
      (node (ref "U3") (pin "9") (pinfunction "EP_9") (pintype "power_in"))
      (node (ref "X1") (pin "2") (pinfunction "2_2") (pintype "passive"))
      (node (ref "X1") (pin "4") (pinfunction "4_4") (pintype "passive"))
    )
    (net (code "18") (name "HAPTIC_EN") (class "Default")
      (node (ref "IC2") (pin "A1") (pinfunction "EN_A1") (pintype "bidirectional"))
      (node (ref "U$1") (pin "P$U1") (pinfunction "P0.12_P$U1") (pintype "bidirectional"))
    )
    (net (code "19") (name "IMU_INT1") (class "Default")
      (node (ref "IC3") (pin "5") (pinfunction "INT1_5") (pintype "bidirectional"))
      (node (ref "U$1") (pin "P$N1") (pinfunction "P0.08_P$N1") (pintype "bidirectional"))
    )
    (net (code "20") (name "IMU_INT2") (class "Default")
      (node (ref "IC3") (pin "6") (pinfunction "INT2_6") (pintype "bidirectional"))
      (node (ref "U$1") (pin "P$P2") (pinfunction "P1.08_P$P2") (pintype "bidirectional"))
    )
    (net (code "21") (name "LX1") (class "Default")
      (node (ref "IC9") (pin "B2") (pinfunction "SW1_1_B2") (pintype "bidirectional"))
      (node (ref "IC9") (pin "B3") (pinfunction "SW1_2_B3") (pintype "bidirectional"))
      (node (ref "L7") (pin "1") (pinfunction "1_1") (pintype "bidirectional"))
    )
    (net (code "22") (name "LX2") (class "Default")
      (node (ref "IC9") (pin "D2") (pinfunction "SW2_1_D2") (pintype "bidirectional"))
      (node (ref "IC9") (pin "D3") (pinfunction "SW2_2_D3") (pintype "bidirectional"))
      (node (ref "L7") (pin "2") (pinfunction "2_2") (pintype "bidirectional"))
    )
    (net (code "23") (name "MOSI") (class "Default")
      (node (ref "J1") (pin "14") (pinfunction "14_14") (pintype "bidirectional"))
      (node (ref "U$1") (pin "P$B13") (pinfunction "P0.03/AIN1_P$B13") (pintype "bidirectional"))
    )
    (net (code "24") (name "Net-(D2-K)") (class "Default")
      (node (ref "C2-EP-DR") (pin "1") (pinfunction "1_1") (pintype "passive"))
      (node (ref "D2") (pin "1") (pinfunction "K_1") (pintype "bidirectional"))
      (node (ref "D4") (pin "2") (pinfunction "A_2") (pintype "bidirectional"))
    )
    (net (code "25") (name "Net-(D5-A)") (class "Default")
      (node (ref "C2-EP-DR") (pin "2") (pinfunction "2_2") (pintype "passive"))
      (node (ref "D5") (pin "2") (pinfunction "A_2") (pintype "bidirectional"))
      (node (ref "L5") (pin "1") (pinfunction "1_1") (pintype "passive"))
      (node (ref "Q3") (pin "3") (pinfunction "D_3") (pintype "bidirectional"))
    )
    (net (code "26") (name "Net-(EPD_C1-Pad1)") (class "Default")
      (node (ref "EPD_C1") (pin "1") (pinfunction "1_1") (pintype "passive"))
      (node (ref "J1") (pin "5") (pinfunction "5_5") (pintype "bidirectional"))
    )
    (net (code "27") (name "Net-(EPD_C2-Pad1)") (class "Default")
      (node (ref "EPD_C2") (pin "1") (pinfunction "1_1") (pintype "passive"))
      (node (ref "J1") (pin "4") (pinfunction "4_4") (pintype "bidirectional"))
    )
    (net (code "28") (name "Net-(EPD_C6-Pad1)") (class "Default")
      (node (ref "EPD_C6") (pin "1") (pinfunction "1_1") (pintype "passive"))
      (node (ref "J1") (pin "18") (pinfunction "18_18") (pintype "bidirectional"))
    )
    (net (code "29") (name "Net-(EPD_C7-Pad1)") (class "Default")
      (node (ref "EPD_C7") (pin "1") (pinfunction "1_1") (pintype "passive"))
      (node (ref "J1") (pin "19") (pinfunction "19_19") (pintype "bidirectional"))
    )
    (net (code "30") (name "Net-(EPD_C8-Pad1)") (class "Default")
      (node (ref "EPD_C8") (pin "1") (pinfunction "1_1") (pintype "passive"))
      (node (ref "J1") (pin "20") (pinfunction "20_20") (pintype "bidirectional"))
    )
    (net (code "31") (name "Net-(EPD_C10-Pad1)") (class "Default")
      (node (ref "EPD_C10") (pin "1") (pinfunction "1_1") (pintype "passive"))
      (node (ref "J1") (pin "22") (pinfunction "22_22") (pintype "bidirectional"))
    )
    (net (code "32") (name "Net-(EPD_C12-Pad1)") (class "Default")
      (node (ref "EPD_C12") (pin "1") (pinfunction "1_1") (pintype "passive"))
      (node (ref "J1") (pin "24") (pinfunction "24_24") (pintype "bidirectional"))
    )
    (net (code "33") (name "Net-(IC1-TS{slash}MR)") (class "Default")
      (node (ref "IC1") (pin "D1") (pinfunction "TS/MR_D1") (pintype "bidirectional"))
      (node (ref "R9") (pin "2") (pinfunction "2_2") (pintype "bidirectional"))
    )
    (net (code "34") (name "Net-(IC2-REG)") (class "Default")
      (node (ref "C32") (pin "2") (pinfunction "2_2") (pintype "passive"))
      (node (ref "IC2") (pin "A2") (pinfunction "REG_A2") (pintype "bidirectional"))
    )
    (net (code "35") (name "Net-(IC3-SDO)") (class "Default")
      (node (ref "IC3") (pin "1") (pinfunction "SDO_1") (pintype "bidirectional"))
      (node (ref "R3") (pin "2") (pinfunction "2_2") (pintype "bidirectional"))
    )
    (net (code "36") (name "Net-(IC9-SCL)") (class "Default")
      (node (ref "IC9") (pin "D1") (pinfunction "SCL_D1") (pintype "bidirectional"))
      (node (ref "R4") (pin "2") (pinfunction "2_2") (pintype "bidirectional"))
    )
    (net (code "37") (name "Net-(IC9-SDA)") (class "Default")
      (node (ref "IC9") (pin "E1") (pinfunction "SDA_E1") (pintype "bidirectional"))
      (node (ref "R2") (pin "2") (pinfunction "2_2") (pintype "bidirectional"))
    )
    (net (code "38") (name "Net-(J4-CC1)") (class "Default")
      (node (ref "J4") (pin "A5") (pinfunction "CC1_A5") (pintype "bidirectional"))
      (node (ref "R1_USB") (pin "2") (pinfunction "2_2") (pintype "bidirectional"))
    )
    (net (code "39") (name "Net-(J4-CC2)") (class "Default")
      (node (ref "J4") (pin "B5") (pinfunction "CC2_B5") (pintype "bidirectional"))
      (node (ref "R2_USB") (pin "1") (pinfunction "1_1") (pintype "bidirectional"))
    )
    (net (code "40") (name "Net-(L2-Pad2)") (class "Default")
      (node (ref "L2") (pin "2") (pinfunction "2_2") (pintype "passive"))
      (node (ref "L3") (pin "1") (pinfunction "1_1") (pintype "passive"))
    )
    (net (code "41") (name "Net-(R1_EP_DR-Pad1)") (class "Default")
      (node (ref "R1_EP_DR") (pin "1") (pinfunction "1_1") (pintype "bidirectional"))
      (node (ref "R_TYPE_SEL") (pin "2") (pinfunction "2_2") (pintype "bidirectional"))
      (node (ref "SJ1") (pin "2") (pinfunction "2_2") (pintype "passive"))
    )
    (net (code "42") (name "Net-(U$1-ANT)") (class "Default")
      (node (ref "C3") (pin "1") (pinfunction "1_1") (pintype "passive"))
      (node (ref "L1") (pin "1") (pinfunction "1_1") (pintype "passive"))
      (node (ref "U$1") (pin "P$H23") (pinfunction "ANT_P$H23") (pintype "bidirectional"))
    )
    (net (code "43") (name "Net-(U$1-DCC)") (class "Default")
      (node (ref "L2") (pin "1") (pinfunction "1_1") (pintype "passive"))
      (node (ref "U$1") (pin "P$B3") (pinfunction "DCC_P$B3") (pintype "output"))
    )
    (net (code "44") (name "Net-(U$1-DEC2)") (class "Default")
      (node (ref "C13") (pin "1") (pinfunction "1_1") (pintype "passive"))
      (node (ref "U$1") (pin "P$A18") (pinfunction "DEC2_P$A18") (pintype "bidirectional"))
    )
    (net (code "45") (name "Net-(U$1-DEC3V3)") (class "Default")
      (node (ref "C20") (pin "1") (pinfunction "1_1") (pintype "passive"))
      (node (ref "U$1") (pin "P$AC5") (pinfunction "DEC3V3_P$AC5") (pintype "bidirectional"))
    )
    (net (code "46") (name "Net-(U$1-DEC5)") (class "Default")
      (node (ref "C9") (pin "1") (pinfunction "1_1") (pintype "passive"))
      (node (ref "U$1") (pin "P$N24") (pinfunction "DEC5_P$N24") (pintype "bidirectional"))
    )
    (net (code "47") (name "Net-(U$1-P0.00{slash}XL1)") (class "Default")
      (node (ref "C17") (pin "2") (pinfunction "2_2") (pintype "passive"))
      (node (ref "U$1") (pin "P$D2") (pinfunction "P0.00/XL1_P$D2") (pintype "bidirectional"))
      (node (ref "X2") (pin "2") (pinfunction "2_2") (pintype "passive"))
    )
    (net (code "48") (name "Net-(U$1-P0.01{slash}XL2)") (class "Default")
      (node (ref "C18") (pin "2") (pinfunction "2_2") (pintype "passive"))
      (node (ref "U$1") (pin "P$F2") (pinfunction "P0.01/XL2_P$F2") (pintype "bidirectional"))
      (node (ref "X2") (pin "1") (pinfunction "1_1") (pintype "passive"))
    )
    (net (code "49") (name "Net-(U$1-XC1)") (class "Default")
      (node (ref "C1") (pin "1") (pinfunction "1_1") (pintype "passive"))
      (node (ref "U$1") (pin "P$B24") (pinfunction "XC1_P$B24") (pintype "input"))
      (node (ref "X1") (pin "1") (pinfunction "1_1") (pintype "passive"))
    )
    (net (code "50") (name "Net-(U$1-XC2)") (class "Default")
      (node (ref "C2") (pin "1") (pinfunction "1_1") (pintype "passive"))
      (node (ref "U$1") (pin "P$A23") (pinfunction "XC2_P$A23") (pintype "output"))
      (node (ref "X1") (pin "3") (pinfunction "3_3") (pintype "passive"))
    )
    (net (code "51") (name "OUT+") (class "Default")
      (node (ref "IC2") (pin "A3") (pinfunction "OUT+_A3") (pintype "bidirectional"))
      (node (ref "TP_OP") (pin "TP") (pinfunction "TP_TP") (pintype "input"))
    )
    (net (code "52") (name "OUT-") (class "Default")
      (node (ref "IC2") (pin "C3") (pinfunction "OUT-_C3") (pintype "bidirectional"))
      (node (ref "TP_ON") (pin "TP") (pinfunction "TP_TP") (pintype "input"))
    )
    (net (code "53") (name "P0.04") (class "Default")
      (node (ref "U$1") (pin "P$J1") (pinfunction "P0.04/AIN2_P$J1") (pintype "bidirectional"))
    )
    (net (code "54") (name "P0.09") (class "Default")
      (node (ref "U$1") (pin "P$L24") (pinfunction "P0.09/NFC1_P$L24") (pintype "bidirectional"))
    )
    (net (code "55") (name "P0.13") (class "Default")
      (node (ref "C30") (pin "2") (pinfunction "2_2") (pintype "passive"))
      (node (ref "R5") (pin "1") (pinfunction "1_1") (pintype "bidirectional"))
      (node (ref "SW_UP") (pin "2") (pinfunction "2_2") (pintype "passive"))
      (node (ref "U$1") (pin "P$AD8") (pinfunction "P0.13_P$AD8") (pintype "bidirectional"))
    )
    (net (code "56") (name "P0.14") (class "Default")
      (node (ref "C31") (pin "2") (pinfunction "2_2") (pintype "passive"))
      (node (ref "R8") (pin "1") (pinfunction "1_1") (pintype "bidirectional"))
      (node (ref "SW_ENT") (pin "2") (pinfunction "2_2") (pintype "passive"))
      (node (ref "U$1") (pin "P$AC9") (pinfunction "P0.14_P$AC9") (pintype "bidirectional"))
    )
    (net (code "57") (name "P0.19") (class "Default")
      (node (ref "U$1") (pin "P$AC15") (pinfunction "P0.19_P$AC15") (pintype "bidirectional"))
    )
    (net (code "58") (name "P0.20") (class "Default")
      (node (ref "U$1") (pin "P$AD16") (pinfunction "P0.20_P$AD16") (pintype "bidirectional"))
    )
    (net (code "59") (name "P0.21") (class "Default")
      (node (ref "U$1") (pin "P$AC17") (pinfunction "P0.21_P$AC17") (pintype "bidirectional"))
    )
    (net (code "60") (name "P0.22") (class "Default")
      (node (ref "U$1") (pin "P$AD18") (pinfunction "P0.22_P$AD18") (pintype "bidirectional"))
    )
    (net (code "61") (name "P0.23") (class "Default")
      (node (ref "U$1") (pin "P$AC19") (pinfunction "P0.23_P$AC19") (pintype "bidirectional"))
    )
    (net (code "62") (name "P0.24") (class "Default")
      (node (ref "U$1") (pin "P$AD20") (pinfunction "P0.24_P$AD20") (pintype "bidirectional"))
    )
    (net (code "63") (name "P0.25") (class "Default")
      (node (ref "U$1") (pin "P$AC21") (pinfunction "P0.25_P$AC21") (pintype "bidirectional"))
    )
    (net (code "64") (name "P0.26") (class "Default")
      (node (ref "U$1") (pin "P$G1") (pinfunction "P0.26_P$G1") (pintype "bidirectional"))
    )
    (net (code "65") (name "P0.27") (class "Default")
      (node (ref "U$1") (pin "P$H2") (pinfunction "P0.27_P$H2") (pintype "bidirectional"))
    )
    (net (code "66") (name "P0.28") (class "Default")
      (node (ref "U$1") (pin "P$B11") (pinfunction "P0.28/AIN4_P$B11") (pintype "bidirectional"))
    )
    (net (code "67") (name "P0.29") (class "Default")
      (node (ref "U$1") (pin "P$A10") (pinfunction "P0.29/AIN5_P$A10") (pintype "bidirectional"))
    )
    (net (code "68") (name "P0.30") (class "Default")
      (node (ref "U$1") (pin "P$B9") (pinfunction "P0.30/AIN6_P$B9") (pintype "bidirectional"))
    )
    (net (code "69") (name "P0.31") (class "Default")
      (node (ref "U$1") (pin "P$A8") (pinfunction "P0.31/AIN7_P$A8") (pintype "bidirectional"))
    )
    (net (code "70") (name "P1.01") (class "Default")
      (node (ref "Q1") (pin "1") (pinfunction "G_1") (pintype "bidirectional"))
      (node (ref "R_PWR_EPD") (pin "1") (pinfunction "1_1") (pintype "bidirectional"))
      (node (ref "U$1") (pin "P$Y23") (pinfunction "P1.01_P$Y23") (pintype "bidirectional"))
    )
    (net (code "71") (name "P1.02") (class "Default")
      (node (ref "C29") (pin "2") (pinfunction "2_2") (pintype "passive"))
      (node (ref "R7") (pin "1") (pinfunction "1_1") (pintype "bidirectional"))
      (node (ref "SW_DN") (pin "2") (pinfunction "2_2") (pintype "passive"))
      (node (ref "U$1") (pin "P$W24") (pinfunction "P1.02_P$W24") (pintype "bidirectional"))
    )
    (net (code "72") (name "P1.03") (class "Default")
      (node (ref "U$1") (pin "P$V23") (pinfunction "P1.03_P$V23") (pintype "bidirectional"))
    )
    (net (code "73") (name "P1.04") (class "Default")
      (node (ref "U$1") (pin "P$U24") (pinfunction "P1.04_P$U24") (pintype "bidirectional"))
    )
    (net (code "74") (name "P1.05") (class "Default")
      (node (ref "U$1") (pin "P$T23") (pinfunction "P1.05_P$T23") (pintype "bidirectional"))
    )
    (net (code "75") (name "P1.06") (class "Default")
      (node (ref "U$1") (pin "P$R24") (pinfunction "P1.06_P$R24") (pintype "bidirectional"))
    )
    (net (code "76") (name "P1.07") (class "Default")
      (node (ref "U$1") (pin "P$P23") (pinfunction "P1.07_P$P23") (pintype "bidirectional"))
    )
    (net (code "77") (name "P1.09") (class "Default")
      (node (ref "U$1") (pin "P$R1") (pinfunction "P1.09_P$R1") (pintype "bidirectional"))
    )
    (net (code "78") (name "P1.10") (class "Default")
      (node (ref "U$1") (pin "P$A20") (pinfunction "P1.10_P$A20") (pintype "bidirectional"))
    )
    (net (code "79") (name "P1.11") (class "Default")
      (node (ref "U$1") (pin "P$B19") (pinfunction "P1.11_P$B19") (pintype "bidirectional"))
    )
    (net (code "80") (name "P1.12") (class "Default")
      (node (ref "U$1") (pin "P$B17") (pinfunction "P1.12_P$B17") (pintype "bidirectional"))
    )
    (net (code "81") (name "P1.13") (class "Default")
      (node (ref "U$1") (pin "P$A16") (pinfunction "P1.13_P$A16") (pintype "bidirectional"))
    )
    (net (code "82") (name "P1.14") (class "Default")
      (node (ref "U$1") (pin "P$B15") (pinfunction "P1.14_P$B15") (pintype "bidirectional"))
    )
    (net (code "83") (name "P1.15") (class "Default")
      (node (ref "U$1") (pin "P$A14") (pinfunction "P1.15_P$A14") (pintype "bidirectional"))
    )
    (net (code "84") (name "PMIC_INT") (class "Default")
      (node (ref "IC1") (pin "A1") (pinfunction "~{INT}_A1") (pintype "bidirectional"))
      (node (ref "U$1") (pin "P$T2") (pinfunction "P0.11_P$T2") (pintype "bidirectional"))
    )
    (net (code "85") (name "PREVGH") (class "Default")
      (node (ref "D5") (pin "1") (pinfunction "K_1") (pintype "bidirectional"))
      (node (ref "EPD_C9") (pin "1") (pinfunction "1_1") (pintype "passive"))
      (node (ref "J1") (pin "21") (pinfunction "21_21") (pintype "bidirectional"))
    )
    (net (code "86") (name "PREVGL") (class "Default")
      (node (ref "D2") (pin "2") (pinfunction "A_2") (pintype "bidirectional"))
      (node (ref "EPD_C11") (pin "1") (pinfunction "1_1") (pintype "passive"))
      (node (ref "J1") (pin "23") (pinfunction "23_23") (pintype "bidirectional"))
    )
    (net (code "87") (name "RESE") (class "Default")
      (node (ref "J1") (pin "3") (pinfunction "3_3") (pintype "bidirectional"))
      (node (ref "Q3") (pin "2") (pinfunction "S_2") (pintype "bidirectional"))
      (node (ref "R1_EP_DR") (pin "2") (pinfunction "2_2") (pintype "bidirectional"))
    )
    (net (code "88") (name "RESET") (class "Default")
      (node (ref "J2") (pin "6") (pinfunction "6_6") (pintype "bidirectional"))
      (node (ref "TP_RESET") (pin "TP") (pinfunction "TP_TP") (pintype "input"))
      (node (ref "U$1") (pin "P$AC13") (pinfunction "P0.18/RESET_P$AC13") (pintype "bidirectional"))
    )
    (net (code "89") (name "RF") (class "Default")
      (node (ref "ANT1") (pin "1") (pinfunction "FEED_1") (pintype "input"))
      (node (ref "C22") (pin "1") (pinfunction "1_1") (pintype "passive"))
      (node (ref "C4") (pin "1") (pinfunction "1_1") (pintype "passive"))
      (node (ref "L1") (pin "2") (pinfunction "2_2") (pintype "passive"))
    )
    (net (code "90") (name "SCK") (class "Default")
      (node (ref "J1") (pin "13") (pinfunction "13_13") (pintype "bidirectional"))
      (node (ref "U$1") (pin "P$A12") (pinfunction "P0.02/AIN0_P$A12") (pintype "bidirectional"))
    )
    (net (code "91") (name "SCL") (class "Default")
      (node (ref "IC1") (pin "B1") (pinfunction "SCL_B1") (pintype "bidirectional"))
      (node (ref "IC2") (pin "C1") (pinfunction "SCL_C1") (pintype "bidirectional"))
      (node (ref "IC3") (pin "12") (pinfunction "SCX_12") (pintype "bidirectional"))
      (node (ref "R17") (pin "2") (pinfunction "2_2") (pintype "bidirectional"))
      (node (ref "R4") (pin "1") (pinfunction "1_1") (pintype "bidirectional"))
      (node (ref "TP_SCL") (pin "TP") (pinfunction "TP_TP") (pintype "input"))
      (node (ref "U$1") (pin "P$M2") (pinfunction "P0.07_P$M2") (pintype "bidirectional"))
      (node (ref "U3") (pin "7") (pinfunction "SCL_7") (pintype "input"))
    )
    (net (code "92") (name "SDA") (class "Default")
      (node (ref "IC1") (pin "C1") (pinfunction "SDA_C1") (pintype "bidirectional"))
      (node (ref "IC2") (pin "B2") (pinfunction "SDA_B2") (pintype "bidirectional"))
      (node (ref "IC3") (pin "2") (pinfunction "SDX_2") (pintype "bidirectional"))
      (node (ref "R18") (pin "2") (pinfunction "2_2") (pintype "bidirectional"))
      (node (ref "R2") (pin "1") (pinfunction "1_1") (pintype "bidirectional"))
      (node (ref "TP_SDA") (pin "TP") (pinfunction "TP_TP") (pintype "input"))
      (node (ref "U$1") (pin "P$L1") (pinfunction "P0.06_P$L1") (pintype "bidirectional"))
      (node (ref "U3") (pin "8") (pinfunction "SDA_8") (pintype "bidirectional"))
    )
    (net (code "93") (name "SWDCLK") (class "Default")
      (node (ref "J2") (pin "4") (pinfunction "4_4") (pintype "bidirectional"))
      (node (ref "TP_SWDCLK") (pin "TP") (pinfunction "TP_TP") (pintype "input"))
      (node (ref "U$1") (pin "P$AA24") (pinfunction "SWDCLK_P$AA24") (pintype "input"))
    )
    (net (code "94") (name "SWDIO") (class "Default")
      (node (ref "J2") (pin "2") (pinfunction "2_2") (pintype "bidirectional"))
      (node (ref "TP_SWDIO") (pin "TP") (pinfunction "TP_TP") (pintype "input"))
      (node (ref "U$1") (pin "P$AC24") (pinfunction "SWDIO_P$AC24") (pintype "bidirectional"))
    )
    (net (code "95") (name "SWO") (class "Default")
      (node (ref "TP_SWO") (pin "TP") (pinfunction "TP_TP") (pintype "input"))
      (node (ref "U$1") (pin "P$AD22") (pinfunction "P1.00_P$AD22") (pintype "bidirectional"))
    )
    (net (code "96") (name "VBAT") (class "Default")
      (node (ref "C27") (pin "2") (pinfunction "2_2") (pintype "passive"))
      (node (ref "C37") (pin "2") (pinfunction "2_2") (pintype "passive"))
      (node (ref "IC1") (pin "C2") (pinfunction "BAT_C2") (pintype "bidirectional"))
      (node (ref "TP_VBAT") (pin "TP") (pinfunction "TP_TP") (pintype "input"))
      (node (ref "U3") (pin "2") (pinfunction "CELL_2") (pintype "power_in"))
      (node (ref "U3") (pin "3") (pinfunction "VDD_3") (pintype "power_in"))
    )
    (net (code "97") (name "VBUS") (class "Default")
      (node (ref "C21") (pin "1") (pinfunction "1_1") (pintype "passive"))
      (node (ref "C38") (pin "2") (pinfunction "2_2") (pintype "passive"))
      (node (ref "C42") (pin "1") (pinfunction "1_1") (pintype "passive"))
      (node (ref "C43") (pin "1") (pinfunction "1_1") (pintype "passive"))
      (node (ref "D3") (pin "5") (pinfunction "VBUS_5") (pintype "bidirectional"))
      (node (ref "IC1") (pin "A2") (pinfunction "IN_A2") (pintype "bidirectional"))
      (node (ref "J4") (pin "A4_B9") (pinfunction "VBUS_A4_B9") (pintype "power_in"))
      (node (ref "J4") (pin "A9_B4") (pinfunction "VBUS_A9_B4") (pintype "power_in"))
      (node (ref "U$1") (pin "P$AD2") (pinfunction "VBUS_P$AD2") (pintype "power_in"))
    )
    (net (code "98") (name "VREG") (class "Default")
      (node (ref "C23") (pin "2") (pinfunction "2_2") (pintype "passive"))
      (node (ref "C24") (pin "1") (pinfunction "1_1") (pintype "passive"))
      (node (ref "C39") (pin "1") (pinfunction "1_1") (pintype "passive"))
      (node (ref "IC1") (pin "B2") (pinfunction "SYS_B2") (pintype "bidirectional"))
      (node (ref "IC9") (pin "A1") (pinfunction "EN_A1") (pintype "bidirectional"))
      (node (ref "IC9") (pin "A2") (pinfunction "VIN_1_A2") (pintype "bidirectional"))
      (node (ref "IC9") (pin "A3") (pinfunction "VIN_2_A3") (pintype "bidirectional"))
      (node (ref "TP_VREG") (pin "TP") (pinfunction "TP_TP") (pintype "input"))
    )
    (net (code "99") (name "unconnected-(ANT1-NC-Pad2)") (class "Default")
      (node (ref "ANT1") (pin "2") (pinfunction "NC_2") (pintype "no_connect"))
    )
    (net (code "100") (name "unconnected-(IC3-ASCL-Pad11)") (class "Default")
      (node (ref "IC3") (pin "11") (pinfunction "ASCL_11") (pintype "bidirectional"))
    )
    (net (code "101") (name "unconnected-(IC3-ASDA-Pad4)") (class "Default")
      (node (ref "IC3") (pin "4") (pinfunction "ASDA_4") (pintype "bidirectional"))
    )
    (net (code "102") (name "unconnected-(J1-Pad1)") (class "Default")
      (node (ref "J1") (pin "1") (pinfunction "1_1") (pintype "bidirectional"))
    )
    (net (code "103") (name "unconnected-(J1-Pad6)") (class "Default")
      (node (ref "J1") (pin "6") (pinfunction "6_6") (pintype "bidirectional"))
    )
    (net (code "104") (name "unconnected-(J1-Pad7)") (class "Default")
      (node (ref "J1") (pin "7") (pinfunction "7_7") (pintype "bidirectional"))
    )
    (net (code "105") (name "unconnected-(J4-SBU1-PadA8)") (class "Default")
      (node (ref "J4") (pin "A8") (pinfunction "SBU1_A8") (pintype "bidirectional"))
    )
    (net (code "106") (name "unconnected-(J4-SBU2-PadB8)") (class "Default")
      (node (ref "J4") (pin "B8") (pinfunction "SBU2_B8") (pintype "bidirectional"))
    )
    (net (code "107") (name "unconnected-(U$1-DCCH-PadP$AB2)") (class "Default")
      (node (ref "U$1") (pin "P$AB2") (pinfunction "DCCH_P$AB2") (pintype "bidirectional"))
    )
  )
)
